# humidity.net
KiCad netlist of a schematic drawn in Altium Designer
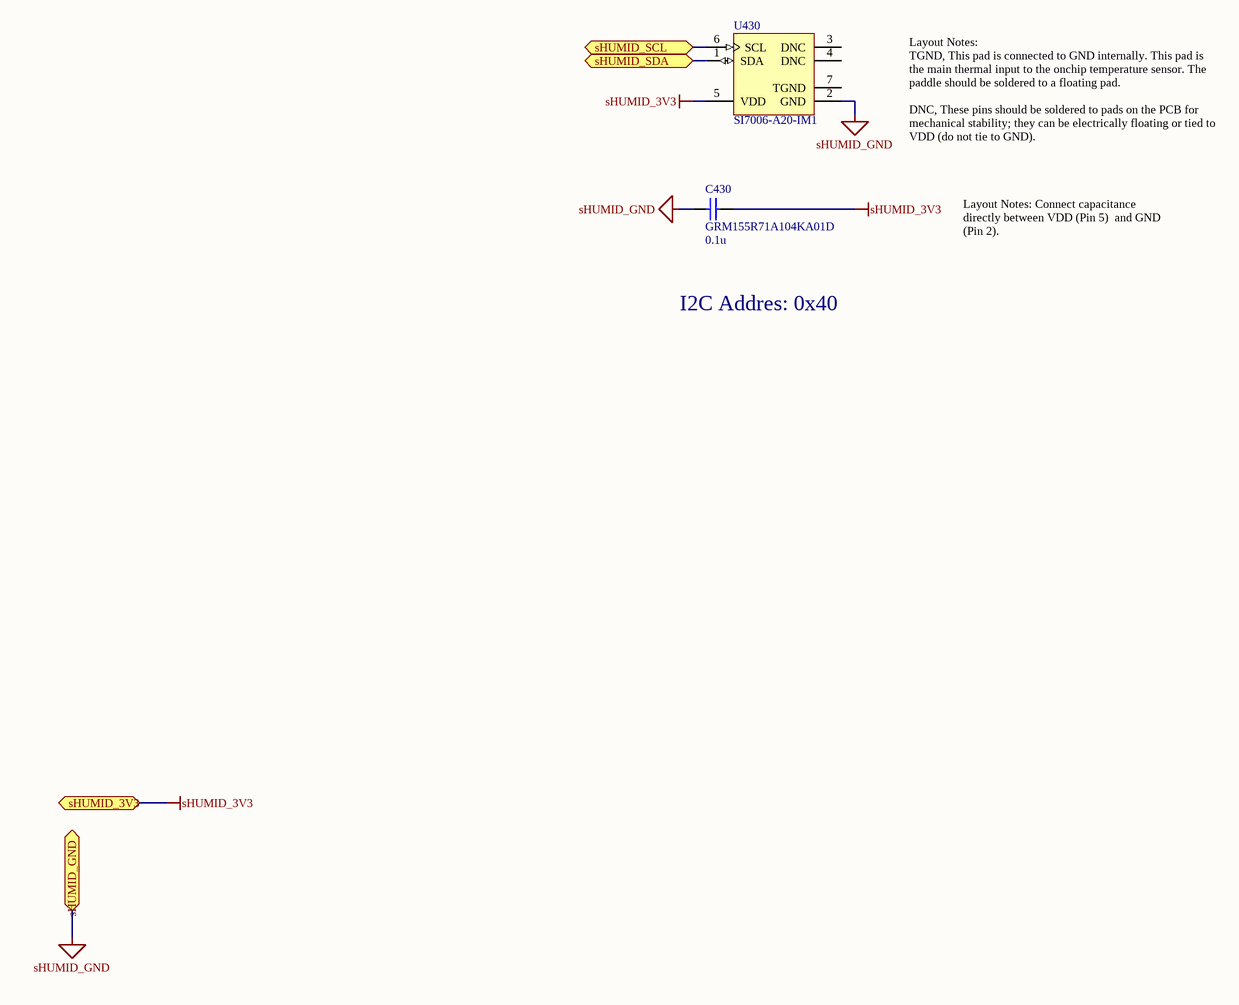
[diagram p0: _humidity.SchDoc]

(export (version "E")
  (design (tool "Eeschema 10.0.6"))
  (components
    (comp (ref "C430")
      (value "GRM155R71A104KA01D")
      (footprint "0402")
      (description "-55-125C, 1005, 10V, X7R, ±10%")
      (fields (field (name "ALTIUM_VALUE") "0.1u"))
      (libsource (lib "standard_capacitors") (part "GRM155R71AxxxKdddd"))
    )
    (comp (ref "U430")
      (value "SI7006-A20-IM1")
      (footprint "SLAB-DFN-6-1500X2400TP_V")
      (description "I2C Humidity and Temperature Sensor, 1.9 to 3.6 V, -40 to 125 degC, 6-Pin DFN, RoHS, Tube")
      (fields (field (name "MANUFACTURER") "Silicon Labs"))
      (libsource (lib "Altium Content Vault") (part "CMP-2000-07060-1"))
    )
  )
  (nets
    (net (code "1") (name "/sHUMID_SCL") (class "Default")
      (node (ref "U430") (pin "6") (pinfunction "SCL_6") (pintype "input"))
    )
    (net (code "2") (name "/sHUMID_SDA") (class "Default")
      (node (ref "U430") (pin "1") (pinfunction "SDA_1") (pintype "bidirectional"))
    )
    (net (code "3") (name "sHUMID_3V3") (class "Default")
      (node (ref "C430") (pin "2") (pinfunction "2_2") (pintype "passive"))
      (node (ref "U430") (pin "5") (pinfunction "VDD_5") (pintype "power_in"))
    )
    (net (code "4") (name "sHUMID_GND") (class "Default")
      (node (ref "C430") (pin "1") (pinfunction "1_1") (pintype "passive"))
      (node (ref "U430") (pin "2") (pinfunction "GND_2") (pintype "power_in"))
    )
    (net (code "5") (name "unconnected-(U430-DNC-Pad3)") (class "Default")
      (node (ref "U430") (pin "3") (pinfunction "DNC_3") (pintype "passive"))
    )
    (net (code "6") (name "unconnected-(U430-DNC-Pad4)") (class "Default")
      (node (ref "U430") (pin "4") (pinfunction "DNC_4") (pintype "passive"))
    )
    (net (code "7") (name "unconnected-(U430-TGND-Pad7)") (class "Default")
      (node (ref "U430") (pin "7") (pinfunction "TGND_7") (pintype "power_in"))
    )
  )
)
